# Rf_reciever.net
KiCad netlist of a schematic drawn in Altium Designer
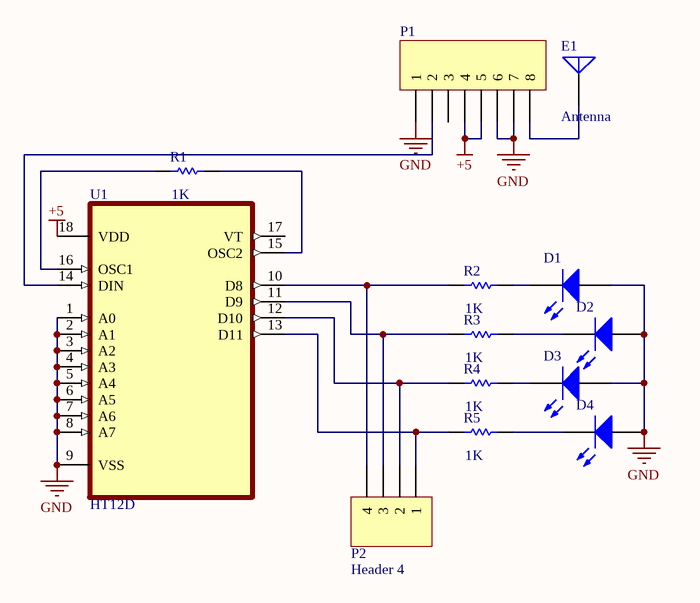
[diagram p0: Rf reciever.SchDoc]

(export (version "E")
  (design (tool "Eeschema 10.0.6"))
  (components
    (comp (ref "D1")
      (value "LED0")
      (footprint "LED-0")
      (description "Typical INFRARED GaAs LED")
      (fields (field (name "PUBLISHER") "Altium Limited"))
      (libsource (lib "Miscellaneous Devices") (part "LED0"))
    )
    (comp (ref "D2")
      (value "LED0")
      (footprint "LED-0")
      (description "Typical INFRARED GaAs LED")
      (fields (field (name "PUBLISHER") "Altium Limited"))
      (libsource (lib "Miscellaneous Devices") (part "LED0"))
    )
    (comp (ref "D3")
      (value "LED0")
      (footprint "LED-0")
      (description "Typical INFRARED GaAs LED")
      (fields (field (name "PUBLISHER") "Altium Limited"))
      (libsource (lib "Miscellaneous Devices") (part "LED0"))
    )
    (comp (ref "D4")
      (value "LED0")
      (footprint "LED-0")
      (description "Typical INFRARED GaAs LED")
      (fields (field (name "PUBLISHER") "Altium Limited"))
      (libsource (lib "Miscellaneous Devices") (part "LED0"))
    )
    (comp (ref "E1")
      (value "Antenna")
      (footprint "PIN1")
      (description "Generic Antenna")
      (fields (field (name "PUBLISHER") "Altium Limited"))
      (libsource (lib "Miscellaneous Devices") (part "Antenna"))
    )
    (comp (ref "P1")
      (value "Header 8")
      (footprint "HDR1X8")
      (description "Header, 8-Pin")
      (fields (field (name "PUBLISHER") "Altium Limited"))
      (libsource (lib "Miscellaneous Connectors") (part "Header 8"))
    )
    (comp (ref "P2")
      (value "Header 4")
      (footprint "HDR1X4")
      (description "Header, 4-Pin")
      (fields (field (name "PUBLISHER") "Altium Limited"))
      (libsource (lib "Miscellaneous Connectors") (part "Header 4"))
    )
    (comp (ref "R1")
      (value "1K")
      (footprint "AXIAL-0.3")
      (description "Resistor")
      (fields (field (name "Comment") "Res1") (field (name "PUBLISHER") "Altium Limited"))
      (libsource (lib "Miscellaneous Devices") (part "Res1"))
    )
    (comp (ref "R2")
      (value "1K")
      (footprint "AXIAL-0.3")
      (description "Resistor")
      (fields (field (name "Comment") "Res1") (field (name "PUBLISHER") "Altium Limited"))
      (libsource (lib "Miscellaneous Devices") (part "Res1"))
    )
    (comp (ref "R3")
      (value "1K")
      (footprint "AXIAL-0.3")
      (description "Resistor")
      (fields (field (name "Comment") "Res1") (field (name "PUBLISHER") "Altium Limited"))
      (libsource (lib "Miscellaneous Devices") (part "Res1"))
    )
    (comp (ref "R4")
      (value "1K")
      (footprint "AXIAL-0.3")
      (description "Resistor")
      (fields (field (name "Comment") "Res1") (field (name "PUBLISHER") "Altium Limited"))
      (libsource (lib "Miscellaneous Devices") (part "Res1"))
    )
    (comp (ref "R5")
      (value "1K")
      (footprint "AXIAL-0.3")
      (description "Resistor")
      (fields (field (name "Comment") "Res1") (field (name "PUBLISHER") "Altium Limited"))
      (libsource (lib "Miscellaneous Devices") (part "Res1"))
    )
    (comp (ref "U1")
      (value "HT12D")
      (footprint "DIP254P762X342-18")
      (fields (field (name "MF") "Holtek"))
      (libsource (lib "SnapEDAsch") (part "HT12D"))
    )
  )
  (nets
    (net (code "1") (name "+5") (class "Default")
      (node (ref "P1") (pin "4") (pinfunction "4_4") (pintype "passive"))
      (node (ref "P1") (pin "5") (pinfunction "5_5") (pintype "passive"))
      (node (ref "U1") (pin "18") (pinfunction "VDD_18") (pintype "power_in"))
    )
    (net (code "2") (name "GND") (class "Default")
      (node (ref "D1") (pin "1") (pinfunction "A_1") (pintype "passive"))
      (node (ref "D2") (pin "1") (pinfunction "A_1") (pintype "passive"))
      (node (ref "D3") (pin "1") (pinfunction "A_1") (pintype "passive"))
      (node (ref "D4") (pin "1") (pinfunction "A_1") (pintype "passive"))
      (node (ref "P1") (pin "1") (pinfunction "1_1") (pintype "passive"))
      (node (ref "P1") (pin "6") (pinfunction "6_6") (pintype "passive"))
      (node (ref "P1") (pin "7") (pinfunction "7_7") (pintype "passive"))
      (node (ref "U1") (pin "1") (pinfunction "A0_1") (pintype "input"))
      (node (ref "U1") (pin "2") (pinfunction "A1_2") (pintype "input"))
      (node (ref "U1") (pin "3") (pinfunction "A2_3") (pintype "input"))
      (node (ref "U1") (pin "4") (pinfunction "A3_4") (pintype "input"))
      (node (ref "U1") (pin "5") (pinfunction "A4_5") (pintype "input"))
      (node (ref "U1") (pin "6") (pinfunction "A5_6") (pintype "input"))
      (node (ref "U1") (pin "7") (pinfunction "A6_7") (pintype "input"))
      (node (ref "U1") (pin "8") (pinfunction "A7_8") (pintype "input"))
      (node (ref "U1") (pin "9") (pinfunction "VSS_9") (pintype "power_in"))
    )
    (net (code "3") (name "Net-(D1-K)") (class "Default")
      (node (ref "D1") (pin "2") (pinfunction "K_2") (pintype "passive"))
      (node (ref "R2") (pin "2") (pinfunction "2_2") (pintype "passive"))
    )
    (net (code "4") (name "Net-(D2-K)") (class "Default")
      (node (ref "D2") (pin "2") (pinfunction "K_2") (pintype "passive"))
      (node (ref "R3") (pin "2") (pinfunction "2_2") (pintype "passive"))
    )
    (net (code "5") (name "Net-(D3-K)") (class "Default")
      (node (ref "D3") (pin "2") (pinfunction "K_2") (pintype "passive"))
      (node (ref "R4") (pin "2") (pinfunction "2_2") (pintype "passive"))
    )
    (net (code "6") (name "Net-(D4-K)") (class "Default")
      (node (ref "D4") (pin "2") (pinfunction "K_2") (pintype "passive"))
      (node (ref "R5") (pin "2") (pinfunction "2_2") (pintype "passive"))
    )
    (net (code "7") (name "Net-(E1-A)") (class "Default")
      (node (ref "E1") (pin "1") (pinfunction "A_1") (pintype "passive"))
      (node (ref "P1") (pin "8") (pinfunction "8_8") (pintype "passive"))
    )
    (net (code "8") (name "Net-(U1-D8)") (class "Default")
      (node (ref "P2") (pin "4") (pinfunction "4_4") (pintype "passive"))
      (node (ref "R2") (pin "1") (pinfunction "1_1") (pintype "passive"))
      (node (ref "U1") (pin "10") (pinfunction "D8_10") (pintype "output"))
    )
    (net (code "9") (name "Net-(U1-D9)") (class "Default")
      (node (ref "P2") (pin "3") (pinfunction "3_3") (pintype "passive"))
      (node (ref "R3") (pin "1") (pinfunction "1_1") (pintype "passive"))
      (node (ref "U1") (pin "11") (pinfunction "D9_11") (pintype "output"))
    )
    (net (code "10") (name "Net-(U1-D10)") (class "Default")
      (node (ref "P2") (pin "2") (pinfunction "2_2") (pintype "passive"))
      (node (ref "R4") (pin "1") (pinfunction "1_1") (pintype "passive"))
      (node (ref "U1") (pin "12") (pinfunction "D10_12") (pintype "output"))
    )
    (net (code "11") (name "Net-(U1-D11)") (class "Default")
      (node (ref "P2") (pin "1") (pinfunction "1_1") (pintype "passive"))
      (node (ref "R5") (pin "1") (pinfunction "1_1") (pintype "passive"))
      (node (ref "U1") (pin "13") (pinfunction "D11_13") (pintype "output"))
    )
    (net (code "12") (name "Net-(U1-DIN)") (class "Default")
      (node (ref "P1") (pin "2") (pinfunction "2_2") (pintype "passive"))
      (node (ref "U1") (pin "14") (pinfunction "DIN_14") (pintype "input"))
    )
    (net (code "13") (name "Net-(U1-OSC1)") (class "Default")
      (node (ref "R1") (pin "1") (pinfunction "1_1") (pintype "passive"))
      (node (ref "U1") (pin "16") (pinfunction "OSC1_16") (pintype "input"))
    )
    (net (code "14") (name "Net-(U1-OSC2)") (class "Default")
      (node (ref "R1") (pin "2") (pinfunction "2_2") (pintype "passive"))
      (node (ref "U1") (pin "15") (pinfunction "OSC2_15") (pintype "output"))
    )
    (net (code "15") (name "unconnected-(P1-Pad3)") (class "Default")
      (node (ref "P1") (pin "3") (pinfunction "3_3") (pintype "passive"))
    )
    (net (code "16") (name "unconnected-(U1-VT-Pad17)") (class "Default")
      (node (ref "U1") (pin "17") (pinfunction "VT_17") (pintype "output"))
    )
  )
)
